# observer.net
KiCad netlist of a schematic drawn in EAGLE
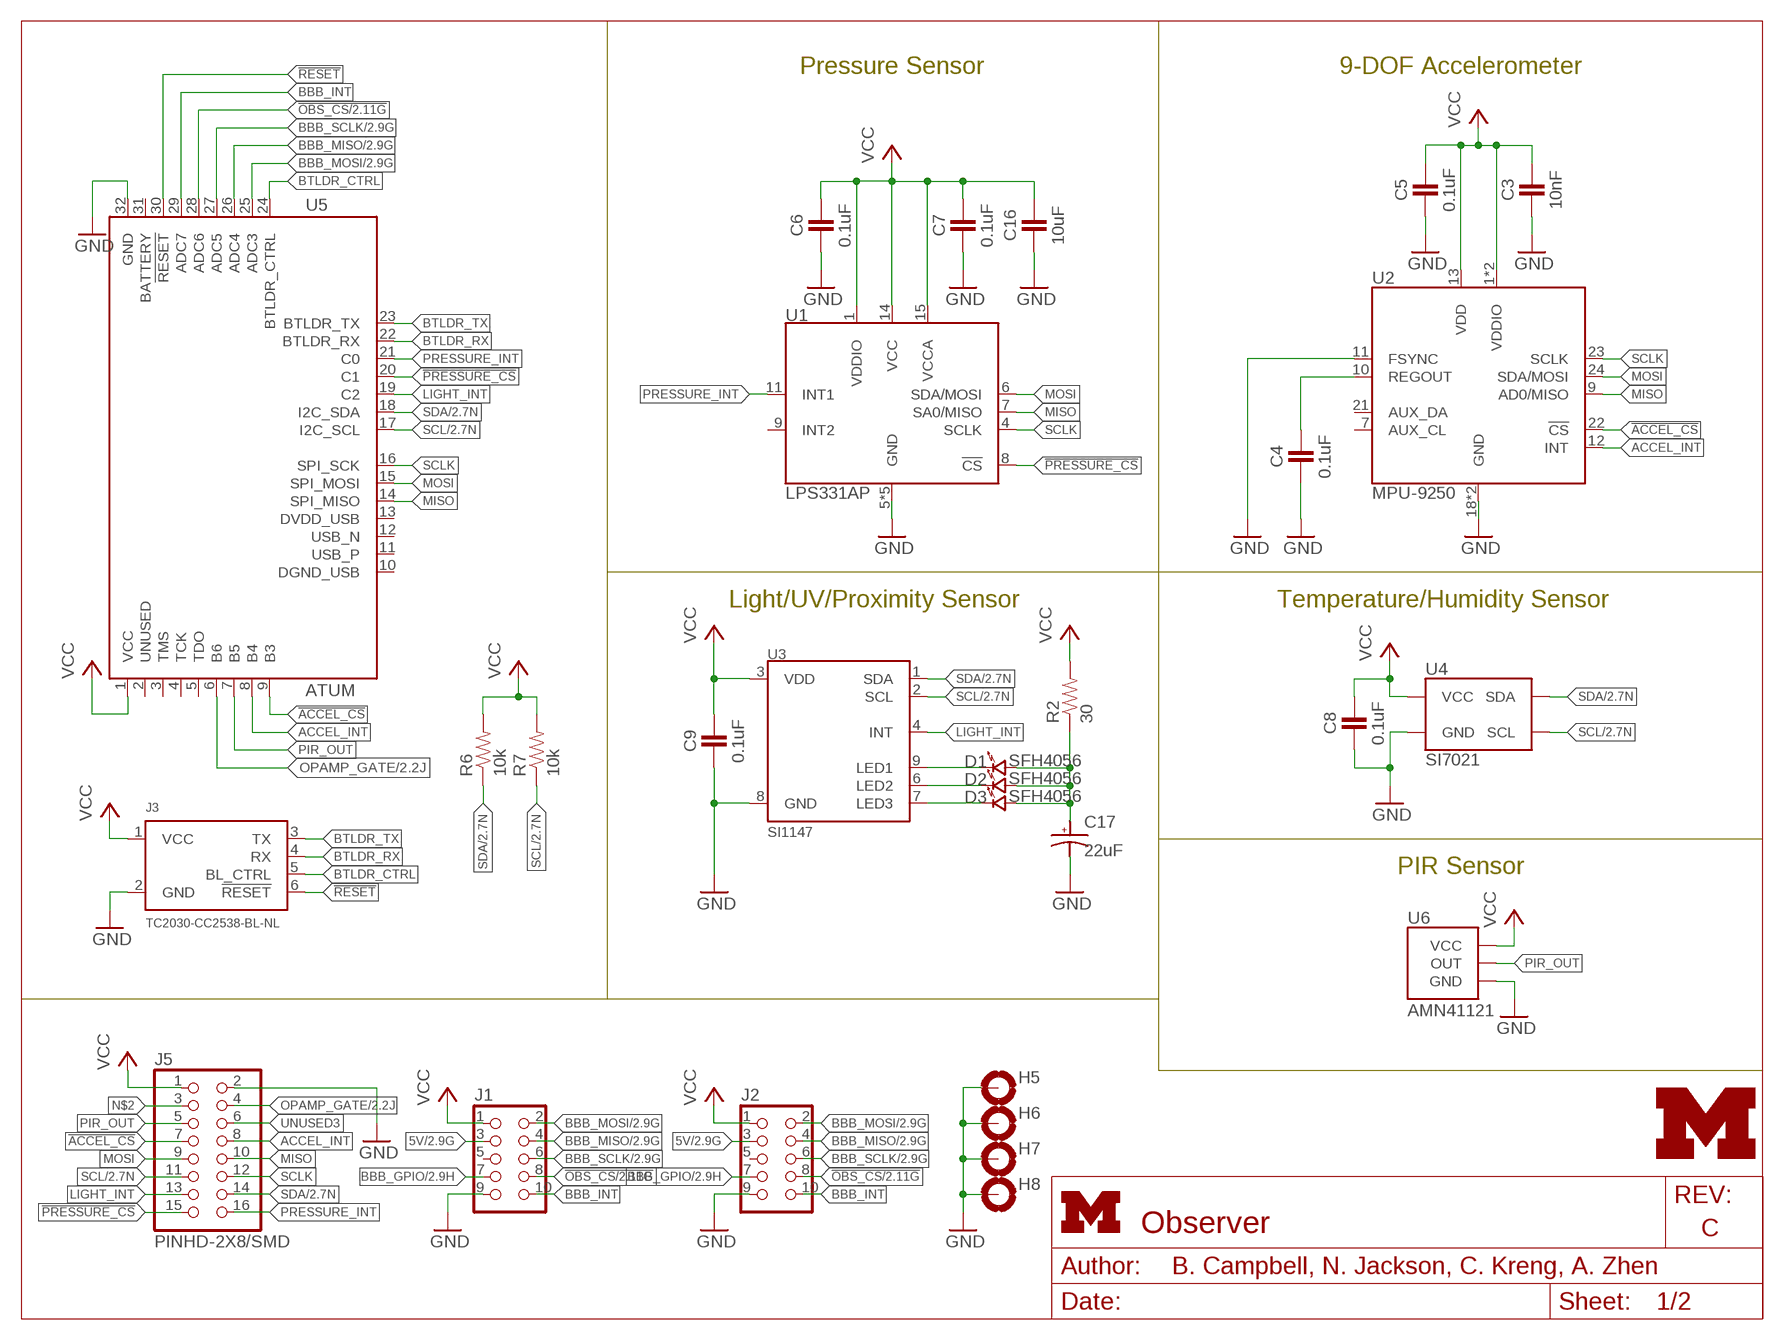
[diagram p0: schematic, sheet 1]
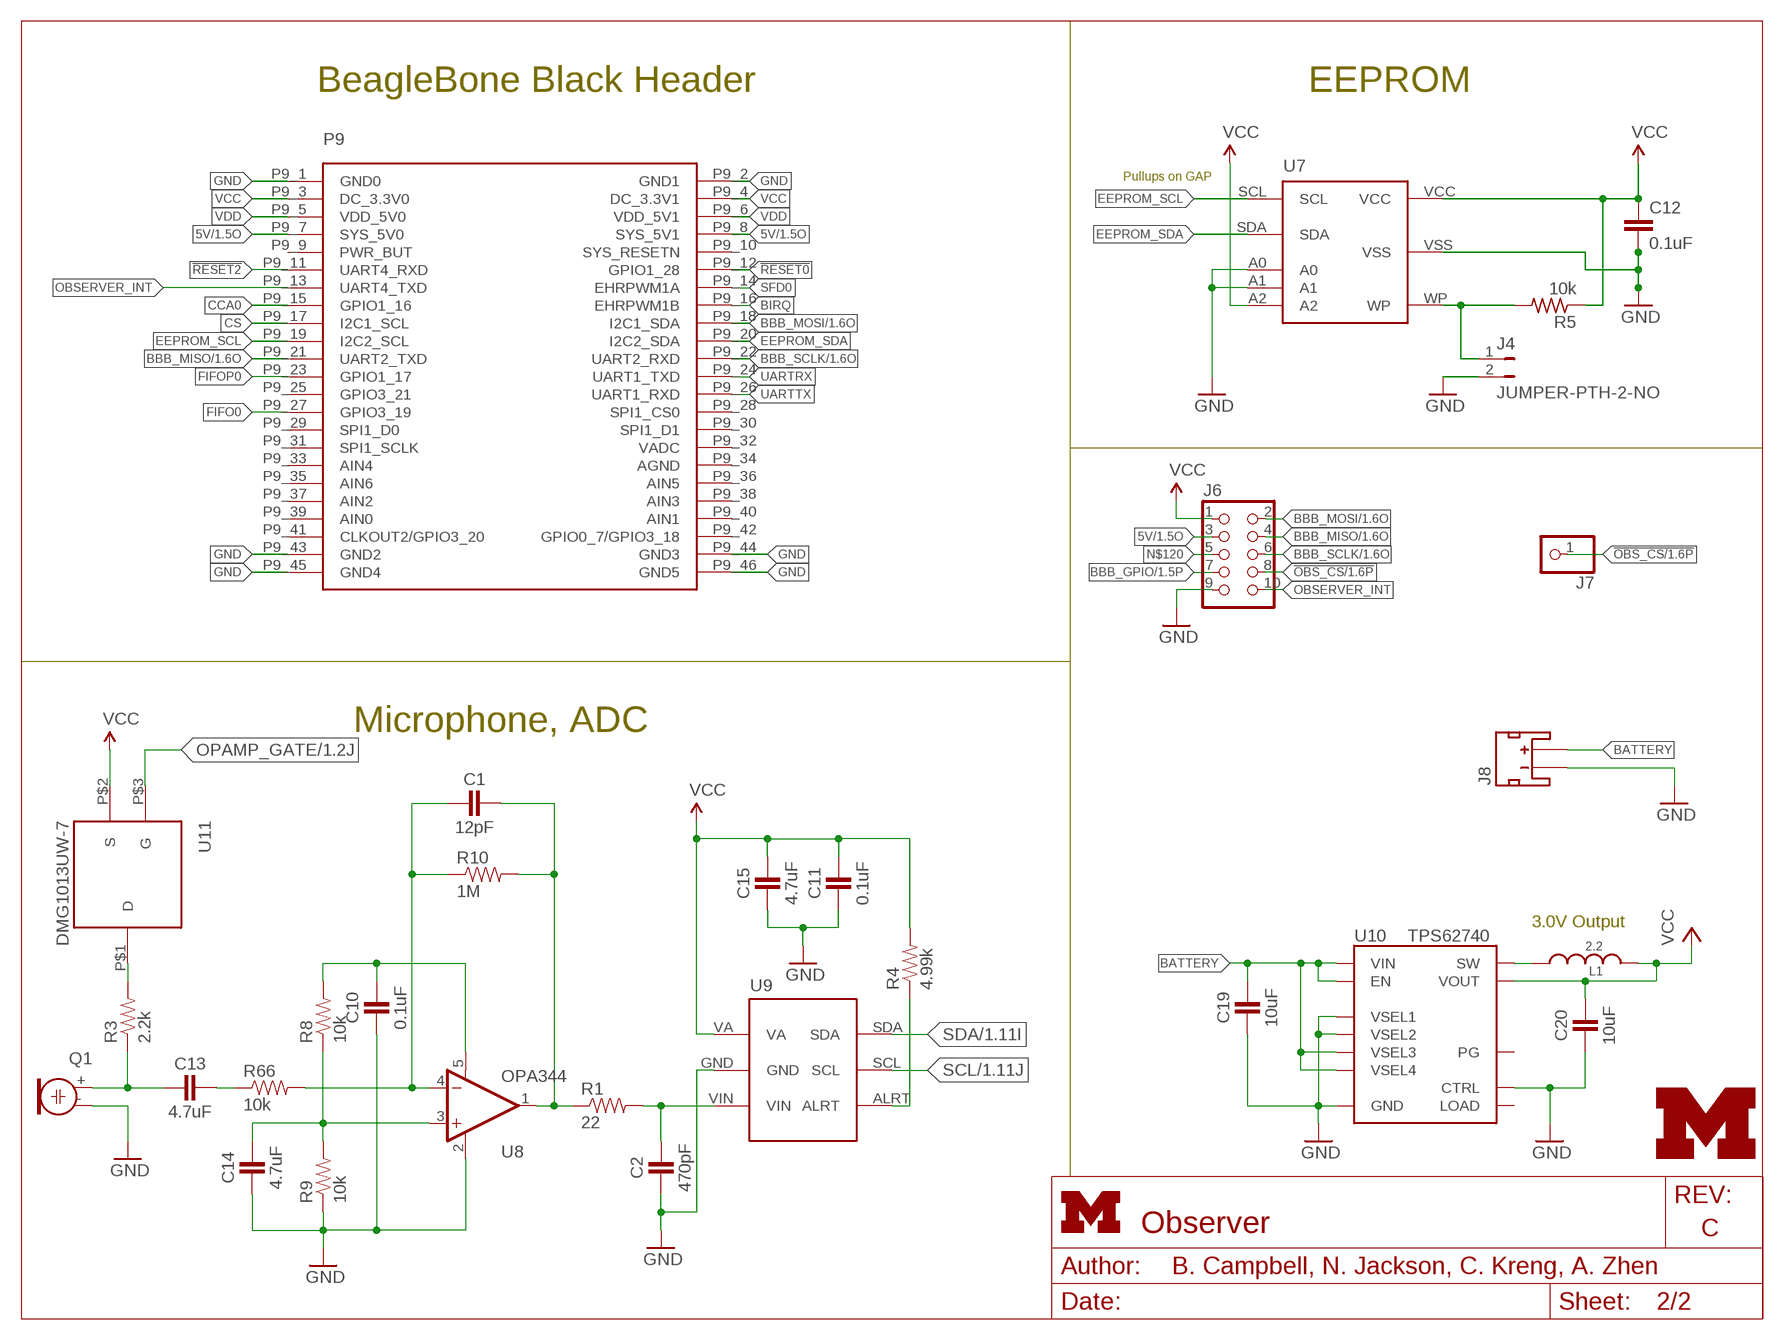
[diagram p1: schematic, sheet 2]

(export (version "E")
  (design (tool "Eeschema 10.0.6"))
  (components
    (comp (ref "C1")
      (value "12pF")
      (footprint "eagle-import:0402_CAP")
      (libsource (lib "eagle-import") (part "CAPACITOR"))
    )
    (comp (ref "C2")
      (value "470pF")
      (footprint "eagle-import:0402_CAP")
      (libsource (lib "eagle-import") (part "CAPACITOR"))
    )
    (comp (ref "C10")
      (value "0.1uF")
      (footprint "eagle-import:0402_CAP")
      (libsource (lib "eagle-import") (part "CAPACITOR"))
    )
    (comp (ref "C11")
      (value "0.1uF")
      (footprint "eagle-import:0402_CAP")
      (libsource (lib "eagle-import") (part "CAPACITOR"))
    )
    (comp (ref "C12")
      (value "0.1uF")
      (footprint "eagle-import:C0402")
      (libsource (lib "eagle-import") (part "C-EUC0402"))
    )
    (comp (ref "C13")
      (value "4.7uF")
      (footprint "eagle-import:0402_CAP")
      (libsource (lib "eagle-import") (part "CAPACITOR"))
    )
    (comp (ref "C14")
      (value "4.7uF")
      (footprint "eagle-import:0402_CAP")
      (libsource (lib "eagle-import") (part "CAPACITOR"))
    )
    (comp (ref "C15")
      (value "4.7uF")
      (footprint "eagle-import:0402_CAP")
      (libsource (lib "eagle-import") (part "CAPACITOR"))
    )
    (comp (ref "C19")
      (value "10uF")
      (footprint "eagle-import:0603_CAP")
      (libsource (lib "eagle-import") (part "CAPACITOR0603_CAP"))
    )
    (comp (ref "C20")
      (value "10uF")
      (footprint "eagle-import:0603_CAP")
      (libsource (lib "eagle-import") (part "CAPACITOR0603_CAP"))
    )
    (comp (ref "J4")
      (value "JUMPER-PTH-2-NO")
      (footprint "eagle-import:PTH-JUMPER-2-NO_NO_SILK")
      (libsource (lib "eagle-import") (part "JUMPER-PTH-2-NO"))
    )
    (comp (ref "J6")
      (value "CON_HEADER_2X05-PTH+SHROUDED_A")
      (footprint "eagle-import:PINSHRD_PTH_2X05")
      (libsource (lib "eagle-import") (part "CON_HEADER_2X05-PTH+SHROUDED_A"))
    )
    (comp (ref "J7")
      (value "PINHD-1X1")
      (footprint "eagle-import:1X01")
      (libsource (lib "eagle-import") (part "PINHD-1X1"))
    )
    (comp (ref "J8")
      (value "JST_2MM_MALE")
      (footprint "eagle-import:JST-2-SMD")
      (libsource (lib "eagle-import") (part "JST_2MM_MALE"))
    )
    (comp (ref "L1")
      (value "2.2")
      (footprint "eagle-import:MIPSZ201D")
      (libsource (lib "eagle-import") (part "MIPSZ2012D"))
    )
    (comp (ref "LOGO2")
      (value "UMICH_SOLID_TINY")
      (footprint "eagle-import:UMICH_SOLID_50MIL")
      (libsource (lib "eagle-import") (part "UMICH_SOLID_TINY"))
    )
    (comp (ref "P9/P8")
      (value "BBB_HEADER")
      (footprint "eagle-import:BBB_HEADERS")
      (libsource (lib "eagle-import") (part "BBB_HEADER"))
    )
    (comp (ref "Q1")
      (value "ELECTRET")
      (footprint "eagle-import:ELECTRET_9.7")
      (libsource (lib "eagle-import") (part "ELECTRET"))
    )
    (comp (ref "R1")
      (value "22")
      (footprint "eagle-import:0402_RES")
      (libsource (lib "eagle-import") (part "RESISTOR0402_RES"))
    )
    (comp (ref "R3")
      (value "2.2k")
      (footprint "eagle-import:0402_RES")
      (libsource (lib "eagle-import") (part "RESISTOR0402_RES"))
    )
    (comp (ref "R4")
      (value "4.99k")
      (footprint "eagle-import:0402_RES")
      (libsource (lib "eagle-import") (part "RESISTOR0402_RES"))
    )
    (comp (ref "R5")
      (value "10k")
      (footprint "eagle-import:R0402")
      (libsource (lib "eagle-import") (part "R-US_R0402"))
    )
    (comp (ref "R8")
      (value "10k")
      (footprint "eagle-import:0402_RES")
      (libsource (lib "eagle-import") (part "RESISTOR0402_RES"))
    )
    (comp (ref "R9")
      (value "10k")
      (footprint "eagle-import:0402_RES")
      (libsource (lib "eagle-import") (part "RESISTOR0402_RES"))
    )
    (comp (ref "R10")
      (value "1M")
      (footprint "eagle-import:0402_RES")
      (libsource (lib "eagle-import") (part "RESISTOR0402_RES"))
    )
    (comp (ref "R66")
      (value "10k")
      (footprint "eagle-import:0402_RES")
      (libsource (lib "eagle-import") (part "RESISTOR0402_RES"))
    )
    (comp (ref "U7")
      (value "CAT24C256WI-GT3")
      (footprint "eagle-import:CAT24C256WI-GT3")
      (libsource (lib "eagle-import") (part "CAT24C256WI-GT3"))
    )
    (comp (ref "U8")
      (value "OPA344")
      (footprint "eagle-import:SOT23-5")
      (libsource (lib "eagle-import") (part "OPA344"))
    )
    (comp (ref "U9")
      (value "ADC121C021")
      (footprint "eagle-import:ADC121C021")
      (libsource (lib "eagle-import") (part "ADC121C021"))
    )
    (comp (ref "U10")
      (value "TPS62740")
      (footprint "eagle-import:R-PWSON-12")
      (libsource (lib "eagle-import") (part "TPS62740"))
    )
    (comp (ref "U11")
      (value "DMG1013UW-7")
      (footprint "eagle-import:SOT-323")
      (libsource (lib "eagle-import") (part "DMG1013UW-7"))
    )
    (comp (ref "C3")
      (value "10nF")
      (footprint "eagle-import:0402_CAP")
      (libsource (lib "eagle-import") (part "CAPACITOR"))
    )
    (comp (ref "C4")
      (value "0.1uF")
      (footprint "eagle-import:0402_CAP")
      (libsource (lib "eagle-import") (part "CAPACITOR"))
    )
    (comp (ref "C5")
      (value "0.1uF")
      (footprint "eagle-import:0402_CAP")
      (libsource (lib "eagle-import") (part "CAPACITOR"))
    )
    (comp (ref "C6")
      (value "0.1uF")
      (footprint "eagle-import:0402_CAP")
      (libsource (lib "eagle-import") (part "CAPACITOR"))
    )
    (comp (ref "C7")
      (value "0.1uF")
      (footprint "eagle-import:0402_CAP")
      (libsource (lib "eagle-import") (part "CAPACITOR"))
    )
    (comp (ref "C8")
      (value "0.1uF")
      (footprint "eagle-import:0402_CAP")
      (libsource (lib "eagle-import") (part "CAPACITOR"))
    )
    (comp (ref "C9")
      (value "0.1uF")
      (footprint "eagle-import:0402_CAP")
      (libsource (lib "eagle-import") (part "CAPACITOR"))
    )
    (comp (ref "C16")
      (value "10uF")
      (footprint "eagle-import:0402_CAP")
      (libsource (lib "eagle-import") (part "CAPACITOR"))
    )
    (comp (ref "C17")
      (value "22uF")
      (footprint "eagle-import:CAP0603")
      (libsource (lib "eagle-import") (part "CAP_POL0603"))
    )
    (comp (ref "D1")
      (value "SFH4056")
      (footprint "eagle-import:SFH4056")
      (libsource (lib "eagle-import") (part "SFH4056"))
    )
    (comp (ref "D2")
      (value "SFH4056")
      (footprint "eagle-import:SFH4056")
      (libsource (lib "eagle-import") (part "SFH4056"))
    )
    (comp (ref "D3")
      (value "SFH4056")
      (footprint "eagle-import:SFH4056")
      (libsource (lib "eagle-import") (part "SFH4056"))
    )
    (comp (ref "H5")
      (value "MOUNT-PAD-ROUND3.2")
      (footprint "eagle-import:3,2-PAD")
      (libsource (lib "eagle-import") (part "MOUNT-PAD-ROUND3.2"))
    )
    (comp (ref "H6")
      (value "MOUNT-PAD-ROUND3.2")
      (footprint "eagle-import:3,2-PAD")
      (libsource (lib "eagle-import") (part "MOUNT-PAD-ROUND3.2"))
    )
    (comp (ref "H7")
      (value "MOUNT-PAD-ROUND3.2")
      (footprint "eagle-import:3,2-PAD")
      (libsource (lib "eagle-import") (part "MOUNT-PAD-ROUND3.2"))
    )
    (comp (ref "H8")
      (value "MOUNT-PAD-ROUND3.2")
      (footprint "eagle-import:3,2-PAD")
      (libsource (lib "eagle-import") (part "MOUNT-PAD-ROUND3.2"))
    )
    (comp (ref "J1")
      (value "CON_HEADER_2X05-SMD+SHROUDED")
      (footprint "eagle-import:PINSHRD_SMT_2X05")
      (libsource (lib "eagle-import") (part "CON_HEADER_2X05-SMD+SHROUDED"))
    )
    (comp (ref "J2")
      (value "CON_HEADER_2X05-SMD+SHROUDED")
      (footprint "eagle-import:PINSHRD_SMT_2X05")
      (libsource (lib "eagle-import") (part "CON_HEADER_2X05-SMD+SHROUDED"))
    )
    (comp (ref "J3")
      (value "TC2030-CC2538-BL-NL")
      (footprint "eagle-import:TC2030-IDC-NL")
      (libsource (lib "eagle-import") (part "TC2030-CC2538-BL-NL"))
    )
    (comp (ref "J5")
      (value "PINHD-2X8/SMD")
      (footprint "eagle-import:2X8_SMD")
      (libsource (lib "eagle-import") (part "PINHD-2X8/SMD"))
    )
    (comp (ref "LOGO1")
      (value "UMICH_SOLID_TINY")
      (footprint "eagle-import:UMICH_SOLID_50MIL")
      (libsource (lib "eagle-import") (part "UMICH_SOLID_TINY"))
    )
    (comp (ref "R2")
      (value "30")
      (footprint "eagle-import:0402_RES")
      (libsource (lib "eagle-import") (part "RESISTOR0402_RES"))
    )
    (comp (ref "R6")
      (value "10k")
      (footprint "eagle-import:0402_RES")
      (libsource (lib "eagle-import") (part "RESISTOR0402_RES"))
    )
    (comp (ref "R7")
      (value "10k")
      (footprint "eagle-import:0402_RES")
      (libsource (lib "eagle-import") (part "RESISTOR0402_RES"))
    )
    (comp (ref "U1")
      (value "LPS331AP")
      (footprint "eagle-import:HCLGA-16_3MM")
      (libsource (lib "eagle-import") (part "LPS331AP"))
    )
    (comp (ref "U2")
      (value "MPU-9250")
      (footprint "eagle-import:QFN-24_3MM")
      (libsource (lib "eagle-import") (part "MPU-9250"))
    )
    (comp (ref "U3")
      (value "SI1147")
      (footprint "eagle-import:QFN-10_2MM")
      (libsource (lib "eagle-import") (part "SI1147"))
    )
    (comp (ref "U4")
      (value "SI7021")
      (footprint "eagle-import:DFN-6_3MM")
      (libsource (lib "eagle-import") (part "SI7021"))
    )
    (comp (ref "U5")
      (value "ATUM")
      (footprint "eagle-import:ATUM")
      (libsource (lib "eagle-import") (part "ATUM"))
    )
    (comp (ref "U6")
      (value "AMN41121")
      (footprint "eagle-import:AMN2")
      (libsource (lib "eagle-import") (part "AMN41121"))
    )
  )
  (nets
    (net (code "1") (name "5V") (class "Default")
      (node (ref "J1") (pin "3") (pinfunction "3_3") (pintype "passive"))
      (node (ref "J2") (pin "3") (pinfunction "3_3") (pintype "passive"))
      (node (ref "J6") (pin "3") (pinfunction "3_3") (pintype "passive"))
      (node (ref "P9/P8") (pin "P9_7") (pinfunction "SYS_5V0_P9_7") (pintype "bidirectional"))
      (node (ref "P9/P8") (pin "P9_8") (pinfunction "SYS_5V1_P9_8") (pintype "bidirectional"))
    )
    (net (code "2") (name "ACCEL_INT") (class "Default")
      (node (ref "J5") (pin "8") (pinfunction "8_8") (pintype "passive"))
      (node (ref "U2") (pin "12") (pinfunction "INT_12") (pintype "bidirectional"))
      (node (ref "U5") (pin "8") (pinfunction "B4_8") (pintype "bidirectional"))
    )
    (net (code "3") (name "BATTERY") (class "Default")
      (node (ref "C19") (pin "1") (pinfunction "1_1") (pintype "bidirectional"))
      (node (ref "J8") (pin "2") (pinfunction "+_2") (pintype "bidirectional"))
      (node (ref "U10") (pin "1") (pinfunction "VIN_1") (pintype "bidirectional"))
      (node (ref "U10") (pin "12") (pinfunction "EN_12") (pintype "bidirectional"))
      (node (ref "U10") (pin "8") (pinfunction "VSEL4_8") (pintype "bidirectional"))
      (node (ref "U10") (pin "9") (pinfunction "VSEL3_9") (pintype "bidirectional"))
    )
    (net (code "4") (name "BBB_GPIO") (class "Default")
      (node (ref "J1") (pin "7") (pinfunction "7_7") (pintype "passive"))
      (node (ref "J2") (pin "7") (pinfunction "7_7") (pintype "passive"))
      (node (ref "J6") (pin "7") (pinfunction "7_7") (pintype "passive"))
    )
    (net (code "5") (name "BBB_INT") (class "Default")
      (node (ref "J1") (pin "10") (pinfunction "10_10") (pintype "passive"))
      (node (ref "J2") (pin "10") (pinfunction "10_10") (pintype "passive"))
      (node (ref "U5") (pin "29") (pinfunction "ADC7_29") (pintype "bidirectional"))
    )
    (net (code "6") (name "BBB_MISO") (class "Default")
      (node (ref "J1") (pin "4") (pinfunction "4_4") (pintype "passive"))
      (node (ref "J2") (pin "4") (pinfunction "4_4") (pintype "passive"))
      (node (ref "J6") (pin "4") (pinfunction "4_4") (pintype "passive"))
      (node (ref "P9/P8") (pin "P9_21") (pinfunction "UART2_TXD_P9_21") (pintype "bidirectional"))
      (node (ref "U5") (pin "26") (pinfunction "ADC4_26") (pintype "bidirectional"))
    )
    (net (code "7") (name "BBB_MOSI") (class "Default")
      (node (ref "J1") (pin "2") (pinfunction "2_2") (pintype "passive"))
      (node (ref "J2") (pin "2") (pinfunction "2_2") (pintype "passive"))
      (node (ref "J6") (pin "2") (pinfunction "2_2") (pintype "passive"))
      (node (ref "P9/P8") (pin "P9_18") (pinfunction "I2C1_SDA_P9_18") (pintype "bidirectional"))
      (node (ref "U5") (pin "25") (pinfunction "ADC3_25") (pintype "bidirectional"))
    )
    (net (code "8") (name "BBB_SCLK") (class "Default")
      (node (ref "J1") (pin "6") (pinfunction "6_6") (pintype "passive"))
      (node (ref "J2") (pin "6") (pinfunction "6_6") (pintype "passive"))
      (node (ref "J6") (pin "6") (pinfunction "6_6") (pintype "passive"))
      (node (ref "P9/P8") (pin "P9_22") (pinfunction "UART2_RXD_P9_22") (pintype "bidirectional"))
      (node (ref "U5") (pin "27") (pinfunction "ADC5_27") (pintype "bidirectional"))
    )
    (net (code "9") (name "BIRQ") (class "Default")
      (node (ref "P9/P8") (pin "P9_16") (pinfunction "EHRPWM1B_P9_16") (pintype "bidirectional"))
    )
    (net (code "10") (name "BTLDR_CTRL") (class "Default")
      (node (ref "J3") (pin "5") (pinfunction "BL_CTRL_5") (pintype "bidirectional"))
      (node (ref "U5") (pin "24") (pinfunction "BTLDR_CTRL_24") (pintype "bidirectional"))
    )
    (net (code "11") (name "BTLDR_RX") (class "Default")
      (node (ref "J3") (pin "4") (pinfunction "RX_4") (pintype "bidirectional"))
      (node (ref "U5") (pin "22") (pinfunction "BTLDR_RX_22") (pintype "bidirectional"))
    )
    (net (code "12") (name "BTLDR_TX") (class "Default")
      (node (ref "J3") (pin "3") (pinfunction "TX_3") (pintype "bidirectional"))
      (node (ref "U5") (pin "23") (pinfunction "BTLDR_TX_23") (pintype "bidirectional"))
    )
    (net (code "13") (name "CCA0") (class "Default")
      (node (ref "P9/P8") (pin "P9_15") (pinfunction "GPIO1_16_P9_15") (pintype "bidirectional"))
    )
    (net (code "14") (name "CS") (class "Default")
      (node (ref "P9/P8") (pin "P9_17") (pinfunction "I2C1_SCL_P9_17") (pintype "bidirectional"))
    )
    (net (code "15") (name "EEPROM_SCL") (class "Default")
      (node (ref "P9/P8") (pin "P9_19") (pinfunction "I2C2_SCL_P9_19") (pintype "bidirectional"))
      (node (ref "U7") (pin "SCL") (pinfunction "SCL_SCL") (pintype "bidirectional"))
    )
    (net (code "16") (name "EEPROM_SDA") (class "Default")
      (node (ref "P9/P8") (pin "P9_20") (pinfunction "I2C2_SDA_P9_20") (pintype "bidirectional"))
      (node (ref "U7") (pin "SDA") (pinfunction "SDA_SDA") (pintype "bidirectional"))
    )
    (net (code "17") (name "FIFO0") (class "Default")
      (node (ref "P9/P8") (pin "P9_27") (pinfunction "GPIO3_19_P9_27") (pintype "bidirectional"))
    )
    (net (code "18") (name "FIFOP0") (class "Default")
      (node (ref "P9/P8") (pin "P9_23") (pinfunction "GPIO1_17_P9_23") (pintype "bidirectional"))
    )
    (net (code "19") (name "GND") (class "Default")
      (node (ref "C10") (pin "2") (pinfunction "2_2") (pintype "bidirectional"))
      (node (ref "C11") (pin "2") (pinfunction "2_2") (pintype "bidirectional"))
      (node (ref "C12") (pin "2") (pinfunction "2_2") (pintype "passive"))
      (node (ref "C14") (pin "2") (pinfunction "2_2") (pintype "bidirectional"))
      (node (ref "C15") (pin "2") (pinfunction "2_2") (pintype "bidirectional"))
      (node (ref "C16") (pin "2") (pinfunction "2_2") (pintype "bidirectional"))
      (node (ref "C17") (pin "NEG") (pinfunction "ANODE_NEG") (pintype "bidirectional"))
      (node (ref "C19") (pin "2") (pinfunction "2_2") (pintype "bidirectional"))
      (node (ref "C2") (pin "2") (pinfunction "2_2") (pintype "bidirectional"))
      (node (ref "C20") (pin "2") (pinfunction "2_2") (pintype "bidirectional"))
      (node (ref "C3") (pin "2") (pinfunction "2_2") (pintype "bidirectional"))
      (node (ref "C4") (pin "2") (pinfunction "2_2") (pintype "bidirectional"))
      (node (ref "C5") (pin "2") (pinfunction "2_2") (pintype "bidirectional"))
      (node (ref "C6") (pin "2") (pinfunction "2_2") (pintype "bidirectional"))
      (node (ref "C7") (pin "2") (pinfunction "2_2") (pintype "bidirectional"))
      (node (ref "C8") (pin "2") (pinfunction "2_2") (pintype "bidirectional"))
      (node (ref "C9") (pin "2") (pinfunction "2_2") (pintype "bidirectional"))
      (node (ref "H5") (pin "B3,2") (pinfunction "MOUNT_B3,2") (pintype "passive"))
      (node (ref "H6") (pin "B3,2") (pinfunction "MOUNT_B3,2") (pintype "passive"))
      (node (ref "H7") (pin "B3,2") (pinfunction "MOUNT_B3,2") (pintype "passive"))
      (node (ref "H8") (pin "B3,2") (pinfunction "MOUNT_B3,2") (pintype "passive"))
      (node (ref "J1") (pin "9") (pinfunction "9_9") (pintype "passive"))
      (node (ref "J2") (pin "9") (pinfunction "9_9") (pintype "passive"))
      (node (ref "J3") (pin "2") (pinfunction "GND_2") (pintype "bidirectional"))
      (node (ref "J4") (pin "2") (pinfunction "2_2") (pintype "passive"))
      (node (ref "J5") (pin "2") (pinfunction "2_2") (pintype "passive"))
      (node (ref "J6") (pin "9") (pinfunction "9_9") (pintype "passive"))
      (node (ref "J8") (pin "1") (pinfunction "-_1") (pintype "bidirectional"))
      (node (ref "P9/P8") (pin "P9_1") (pinfunction "GND0_P9_1") (pintype "bidirectional"))
      (node (ref "P9/P8") (pin "P9_2") (pinfunction "GND1_P9_2") (pintype "bidirectional"))
      (node (ref "P9/P8") (pin "P9_43") (pinfunction "GND2_P9_43") (pintype "bidirectional"))
      (node (ref "P9/P8") (pin "P9_44") (pinfunction "GND3_P9_44") (pintype "bidirectional"))
      (node (ref "P9/P8") (pin "P9_45") (pinfunction "GND4_P9_45") (pintype "bidirectional"))
      (node (ref "P9/P8") (pin "P9_46") (pinfunction "GND5_P9_46") (pintype "bidirectional"))
      (node (ref "Q1") (pin "-") (pinfunction "1_-") (pintype "passive"))
      (node (ref "R9") (pin "1") (pinfunction "1_1") (pintype "passive"))
      (node (ref "U1") (pin "10") (pinfunction "GND_10") (pintype "bidirectional"))
      (node (ref "U1") (pin "12") (pinfunction "GND_12") (pintype "bidirectional"))
      (node (ref "U1") (pin "13") (pinfunction "GND_13") (pintype "bidirectional"))
      (node (ref "U1") (pin "16") (pinfunction "GND_16") (pintype "bidirectional"))
      (node (ref "U1") (pin "5") (pinfunction "GND_5") (pintype "bidirectional"))
      (node (ref "U10") (pin "10") (pinfunction "VSEL2_10") (pintype "bidirectional"))
      (node (ref "U10") (pin "11") (pinfunction "VSEL1_11") (pintype "bidirectional"))
      (node (ref "U10") (pin "3") (pinfunction "GND_3") (pintype "bidirectional"))
      (node (ref "U10") (pin "4") (pinfunction "CTRL_4") (pintype "bidirectional"))
      (node (ref "U10") (pin "NC") (pinfunction "GND_NC") (pintype "bidirectional"))
      (node (ref "U2") (pin "11") (pinfunction "FSYNC_11") (pintype "bidirectional"))
      (node (ref "U2") (pin "18") (pinfunction "GND_18") (pintype "bidirectional"))
      (node (ref "U2") (pin "20") (pinfunction "GND_20") (pintype "bidirectional"))
      (node (ref "U3") (pin "8") (pinfunction "GND_8") (pintype "bidirectional"))
      (node (ref "U4") (pin "2") (pinfunction "GND_2") (pintype "bidirectional"))
      (node (ref "U5") (pin "32") (pinfunction "GND_32") (pintype "bidirectional"))
      (node (ref "U6") (pin "GND") (pinfunction "GND_GND") (pintype "bidirectional"))
      (node (ref "U7") (pin "A0") (pinfunction "A0_A0") (pintype "bidirectional"))
      (node (ref "U7") (pin "A1") (pinfunction "A1_A1") (pintype "bidirectional"))
      (node (ref "U7") (pin "VSS") (pinfunction "VSS_VSS") (pintype "bidirectional"))
      (node (ref "U8") (pin "2") (pinfunction "V-_2") (pintype "power_in"))
      (node (ref "U9") (pin "GND") (pinfunction "GND_GND") (pintype "bidirectional"))
    )
    (net (code "20") (name "LIGHT_INT") (class "Default")
      (node (ref "J5") (pin "13") (pinfunction "13_13") (pintype "passive"))
      (node (ref "U3") (pin "4") (pinfunction "INT_4") (pintype "bidirectional"))
      (node (ref "U5") (pin "19") (pinfunction "C2_19") (pintype "bidirectional"))
    )
    (net (code "21") (name "MISO") (class "Default")
      (node (ref "J5") (pin "10") (pinfunction "10_10") (pintype "passive"))
      (node (ref "U1") (pin "7") (pinfunction "SA0/MISO_7") (pintype "bidirectional"))
      (node (ref "U2") (pin "9") (pinfunction "AD0/MISO_9") (pintype "bidirectional"))
      (node (ref "U5") (pin "14") (pinfunction "SPI_MISO_14") (pintype "bidirectional"))
    )
    (net (code "22") (name "MOSI") (class "Default")
      (node (ref "J5") (pin "9") (pinfunction "9_9") (pintype "passive"))
      (node (ref "U1") (pin "6") (pinfunction "SDA/MOSI_6") (pintype "bidirectional"))
      (node (ref "U2") (pin "24") (pinfunction "SDA/MOSI_24") (pintype "bidirectional"))
      (node (ref "U5") (pin "15") (pinfunction "SPI_MOSI_15") (pintype "bidirectional"))
    )
    (net (code "23") (name "N$2") (class "Default")
      (node (ref "J5") (pin "3") (pinfunction "3_3") (pintype "passive"))
    )
    (net (code "24") (name "N$120") (class "Default")
      (node (ref "J6") (pin "5") (pinfunction "5_5") (pintype "passive"))
    )
    (net (code "25") (name "Net-(C2-Pad1)") (class "Default")
      (node (ref "C2") (pin "1") (pinfunction "1_1") (pintype "bidirectional"))
      (node (ref "R1") (pin "2") (pinfunction "2_2") (pintype "passive"))
      (node (ref "U9") (pin "VIN") (pinfunction "VIN_VIN") (pintype "bidirectional"))
    )
    (net (code "26") (name "Net-(C13-Pad1)") (class "Default")
      (node (ref "C13") (pin "1") (pinfunction "1_1") (pintype "bidirectional"))
      (node (ref "R66") (pin "1") (pinfunction "1_1") (pintype "passive"))
    )
    (net (code "27") (name "Net-(C17-CATHODE)") (class "Default")
      (node (ref "C17") (pin "POS") (pinfunction "CATHODE_POS") (pintype "bidirectional"))
      (node (ref "D1") (pin "ANODE") (pinfunction "ANODE_ANODE") (pintype "bidirectional"))
      (node (ref "D2") (pin "ANODE") (pinfunction "ANODE_ANODE") (pintype "bidirectional"))
      (node (ref "D3") (pin "ANODE") (pinfunction "ANODE_ANODE") (pintype "bidirectional"))
      (node (ref "R2") (pin "1") (pinfunction "1_1") (pintype "passive"))
    )
    (net (code "28") (name "Net-(J4-Pad1)") (class "Default")
      (node (ref "J4") (pin "1") (pinfunction "1_1") (pintype "passive"))
      (node (ref "R5") (pin "2") (pinfunction "2_2") (pintype "passive"))
      (node (ref "U7") (pin "WP") (pinfunction "WP_WP") (pintype "bidirectional"))
    )
    (net (code "29") (name "Net-(Q1-2)") (class "Default")
      (node (ref "C13") (pin "2") (pinfunction "2_2") (pintype "bidirectional"))
      (node (ref "Q1") (pin "+") (pinfunction "2_+") (pintype "passive"))
      (node (ref "R3") (pin "1") (pinfunction "1_1") (pintype "passive"))
    )
    (net (code "30") (name "Net-(R4-Pad1)") (class "Default")
      (node (ref "R4") (pin "1") (pinfunction "1_1") (pintype "passive"))
      (node (ref "U9") (pin "ALRT") (pinfunction "ALRT_ALRT") (pintype "bidirectional"))
    )
    (net (code "31") (name "Net-(U2-REGOUT)") (class "Default")
      (node (ref "C4") (pin "1") (pinfunction "1_1") (pintype "bidirectional"))
      (node (ref "U2") (pin "10") (pinfunction "REGOUT_10") (pintype "bidirectional"))
    )
    (net (code "32") (name "Net-(U3-LED1)") (class "Default")
      (node (ref "D1") (pin "CATHODE") (pinfunction "CATHODE_CATHODE") (pintype "bidirectional"))
      (node (ref "U3") (pin "9") (pinfunction "LED1_9") (pintype "bidirectional"))
    )
    (net (code "33") (name "Net-(U3-LED2)") (class "Default")
      (node (ref "D2") (pin "CATHODE") (pinfunction "CATHODE_CATHODE") (pintype "bidirectional"))
      (node (ref "U3") (pin "6") (pinfunction "LED2_6") (pintype "bidirectional"))
    )
    (net (code "34") (name "Net-(U3-LED3)") (class "Default")
      (node (ref "D3") (pin "CATHODE") (pinfunction "CATHODE_CATHODE") (pintype "bidirectional"))
      (node (ref "U3") (pin "7") (pinfunction "LED3_7") (pintype "bidirectional"))
    )
    (net (code "35") (name "Net-(U8-+IN)") (class "Default")
      (node (ref "C14") (pin "1") (pinfunction "1_1") (pintype "bidirectional"))
      (node (ref "R8") (pin "1") (pinfunction "1_1") (pintype "passive"))
      (node (ref "R9") (pin "2") (pinfunction "2_2") (pintype "passive"))
      (node (ref "U8") (pin "3") (pinfunction "+IN_3") (pintype "input"))
    )
    (net (code "36") (name "Net-(U8--IN)") (class "Default")
      (node (ref "C1") (pin "2") (pinfunction "2_2") (pintype "bidirectional"))
      (node (ref "R10") (pin "1") (pinfunction "1_1") (pintype "passive"))
      (node (ref "R66") (pin "2") (pinfunction "2_2") (pintype "passive"))
      (node (ref "U8") (pin "4") (pinfunction "-IN_4") (pintype "input"))
    )
    (net (code "37") (name "Net-(U8-OUT)") (class "Default")
      (node (ref "C1") (pin "1") (pinfunction "1_1") (pintype "bidirectional"))
      (node (ref "R1") (pin "1") (pinfunction "1_1") (pintype "passive"))
      (node (ref "R10") (pin "2") (pinfunction "2_2") (pintype "passive"))
      (node (ref "U8") (pin "1") (pinfunction "OUT_1") (pintype "output"))
    )
    (net (code "38") (name "Net-(U8-V+)") (class "Default")
      (node (ref "C10") (pin "1") (pinfunction "1_1") (pintype "bidirectional"))
      (node (ref "R8") (pin "2") (pinfunction "2_2") (pintype "passive"))
      (node (ref "U8") (pin "5") (pinfunction "V+_5") (pintype "power_in"))
    )
    (net (code "39") (name "Net-(U10-SW)") (class "Default")
      (node (ref "L1") (pin "1") (pinfunction "1_1") (pintype "bidirectional"))
      (node (ref "U10") (pin "2") (pinfunction "SW_2") (pintype "bidirectional"))
    )
    (net (code "40") (name "Net-(U11-D)") (class "Default")
      (node (ref "R3") (pin "2") (pinfunction "2_2") (pintype "passive"))
      (node (ref "U11") (pin "P$1") (pinfunction "D_P$1") (pintype "bidirectional"))
    )
    (net (code "41") (name "OBSERVER_INT") (class "Default")
      (node (ref "J6") (pin "10") (pinfunction "10_10") (pintype "passive"))
      (node (ref "P9/P8") (pin "P9_13") (pinfunction "UART4_TXD_P9_13") (pintype "bidirectional"))
    )
    (net (code "42") (name "OPAMP_GATE") (class "Default")
      (node (ref "J5") (pin "4") (pinfunction "4_4") (pintype "passive"))
      (node (ref "U11") (pin "P$3") (pinfunction "G_P$3") (pintype "bidirectional"))
      (node (ref "U5") (pin "6") (pinfunction "B6_6") (pintype "bidirectional"))
    )
    (net (code "43") (name "PIR_OUT") (class "Default")
      (node (ref "J5") (pin "5") (pinfunction "5_5") (pintype "passive"))
      (node (ref "U5") (pin "7") (pinfunction "B5_7") (pintype "bidirectional"))
      (node (ref "U6") (pin "OUT") (pinfunction "OUT_OUT") (pintype "bidirectional"))
    )
    (net (code "44") (name "PRESSURE_INT") (class "Default")
      (node (ref "J5") (pin "16") (pinfunction "16_16") (pintype "passive"))
      (node (ref "U1") (pin "11") (pinfunction "INT1_11") (pintype "bidirectional"))
      (node (ref "U5") (pin "21") (pinfunction "C0_21") (pintype "bidirectional"))
    )
    (net (code "45") (name "SCL") (class "Default")
      (node (ref "J5") (pin "11") (pinfunction "11_11") (pintype "passive"))
      (node (ref "R7") (pin "1") (pinfunction "1_1") (pintype "passive"))
      (node (ref "U3") (pin "2") (pinfunction "SCL_2") (pintype "bidirectional"))
      (node (ref "U4") (pin "6") (pinfunction "SCL_6") (pintype "bidirectional"))
      (node (ref "U5") (pin "17") (pinfunction "I2C_SCL_17") (pintype "bidirectional"))
      (node (ref "U9") (pin "SCL") (pinfunction "SCL_SCL") (pintype "bidirectional"))
    )
    (net (code "46") (name "SCLK") (class "Default")
      (node (ref "J5") (pin "12") (pinfunction "12_12") (pintype "passive"))
      (node (ref "U1") (pin "4") (pinfunction "SCLK_4") (pintype "bidirectional"))
      (node (ref "U2") (pin "23") (pinfunction "SCLK_23") (pintype "bidirectional"))
      (node (ref "U5") (pin "16") (pinfunction "SPI_SCK_16") (pintype "bidirectional"))
    )
    (net (code "47") (name "SDA") (class "Default")
      (node (ref "J5") (pin "14") (pinfunction "14_14") (pintype "passive"))
      (node (ref "R6") (pin "1") (pinfunction "1_1") (pintype "passive"))
      (node (ref "U3") (pin "1") (pinfunction "SDA_1") (pintype "bidirectional"))
      (node (ref "U4") (pin "1") (pinfunction "SDA_1") (pintype "bidirectional"))
      (node (ref "U5") (pin "18") (pinfunction "I2C_SDA_18") (pintype "bidirectional"))
      (node (ref "U9") (pin "SDA") (pinfunction "SDA_SDA") (pintype "bidirectional"))
    )
    (net (code "48") (name "SFD0") (class "Default")
      (node (ref "P9/P8") (pin "P9_14") (pinfunction "EHRPWM1A_P9_14") (pintype "bidirectional"))
    )
    (net (code "49") (name "UARTRX") (class "Default")
      (node (ref "P9/P8") (pin "P9_24") (pinfunction "UART1_TXD_P9_24") (pintype "bidirectional"))
    )
    (net (code "50") (name "UARTTX") (class "Default")
      (node (ref "P9/P8") (pin "P9_26") (pinfunction "UART1_RXD_P9_26") (pintype "bidirectional"))
    )
    (net (code "51") (name "UNUSED3") (class "Default")
      (node (ref "J5") (pin "6") (pinfunction "6_6") (pintype "passive"))
    )
    (net (code "52") (name "VCC") (class "Default")
      (node (ref "C11") (pin "1") (pinfunction "1_1") (pintype "bidirectional"))
      (node (ref "C12") (pin "1") (pinfunction "1_1") (pintype "passive"))
      (node (ref "C15") (pin "1") (pinfunction "1_1") (pintype "bidirectional"))
      (node (ref "C16") (pin "1") (pinfunction "1_1") (pintype "bidirectional"))
      (node (ref "C20") (pin "1") (pinfunction "1_1") (pintype "bidirectional"))
      (node (ref "C3") (pin "1") (pinfunction "1_1") (pintype "bidirectional"))
      (node (ref "C5") (pin "1") (pinfunction "1_1") (pintype "bidirectional"))
      (node (ref "C6") (pin "1") (pinfunction "1_1") (pintype "bidirectional"))
      (node (ref "C7") (pin "1") (pinfunction "1_1") (pintype "bidirectional"))
      (node (ref "C8") (pin "1") (pinfunction "1_1") (pintype "bidirectional"))
      (node (ref "C9") (pin "1") (pinfunction "1_1") (pintype "bidirectional"))
      (node (ref "J1") (pin "1") (pinfunction "1_1") (pintype "passive"))
      (node (ref "J2") (pin "1") (pinfunction "1_1") (pintype "passive"))
      (node (ref "J3") (pin "1") (pinfunction "VCC_1") (pintype "bidirectional"))
      (node (ref "J5") (pin "1") (pinfunction "1_1") (pintype "passive"))
      (node (ref "J6") (pin "1") (pinfunction "1_1") (pintype "passive"))
      (node (ref "L1") (pin "2") (pinfunction "2_2") (pintype "bidirectional"))
      (node (ref "P9/P8") (pin "P9_3") (pinfunction "DC_3.3V0_P9_3") (pintype "bidirectional"))
      (node (ref "P9/P8") (pin "P9_4") (pinfunction "DC_3.3V1_P9_4") (pintype "bidirectional"))
      (node (ref "R2") (pin "2") (pinfunction "2_2") (pintype "passive"))
      (node (ref "R4") (pin "2") (pinfunction "2_2") (pintype "passive"))
      (node (ref "R5") (pin "1") (pinfunction "1_1") (pintype "passive"))
      (node (ref "R6") (pin "2") (pinfunction "2_2") (pintype "passive"))
      (node (ref "R7") (pin "2") (pinfunction "2_2") (pintype "passive"))
      (node (ref "U1") (pin "1") (pinfunction "VDDIO_1") (pintype "bidirectional"))
      (node (ref "U1") (pin "14") (pinfunction "VCC_14") (pintype "bidirectional"))
      (node (ref "U1") (pin "15") (pinfunction "VCCA_15") (pintype "bidirectional"))
      (node (ref "U10") (pin "5") (pinfunction "VOUT_5") (pintype "bidirectional"))
      (node (ref "U11") (pin "P$2") (pinfunction "S_P$2") (pintype "bidirectional"))
      (node (ref "U2") (pin "1") (pinfunction "VDDIO_1") (pintype "bidirectional"))
      (node (ref "U2") (pin "13") (pinfunction "VDD_13") (pintype "bidirectional"))
      (node (ref "U2") (pin "8") (pinfunction "VDDIO_8") (pintype "bidirectional"))
      (node (ref "U3") (pin "3") (pinfunction "VDD_3") (pintype "bidirectional"))
      (node (ref "U4") (pin "5") (pinfunction "VCC_5") (pintype "bidirectional"))
      (node (ref "U5") (pin "1") (pinfunction "VCC_1") (pintype "bidirectional"))
      (node (ref "U6") (pin "VCC") (pinfunction "VCC_VCC") (pintype "bidirectional"))
      (node (ref "U7") (pin "A2") (pinfunction "A2_A2") (pintype "bidirectional"))
      (node (ref "U7") (pin "VCC") (pinfunction "VCC_VCC") (pintype "bidirectional"))
      (node (ref "U9") (pin "VA") (pinfunction "VA_VA") (pintype "bidirectional"))
    )
    (net (code "53") (name "VDD") (class "Default")
      (node (ref "P9/P8") (pin "P9_5") (pinfunction "VDD_5V0_P9_5") (pintype "bidirectional"))
      (node (ref "P9/P8") (pin "P9_6") (pinfunction "VDD_5V1_P9_6") (pintype "bidirectional"))
    )
    (net (code "54") (name "unconnected-(J1-Pad5)") (class "Default")
      (node (ref "J1") (pin "5") (pinfunction "5_5") (pintype "passive"))
    )
    (net (code "55") (name "unconnected-(J2-Pad5)") (class "Default")
      (node (ref "J2") (pin "5") (pinfunction "5_5") (pintype "passive"))
    )
    (net (code "56") (name "unconnected-(J8-PAD1-PadNC1)") (class "Default")
      (node (ref "J8") (pin "NC1") (pinfunction "PAD1_NC1") (pintype "bidirectional"))
    )
    (net (code "57") (name "unconnected-(J8-PAD2-PadNC2)") (class "Default")
      (node (ref "J8") (pin "NC2") (pinfunction "PAD2_NC2") (pintype "bidirectional"))
    )
    (net (code "58") (name "unconnected-(P9/P8-AGND-PadP9_34)") (class "Default")
      (node (ref "P9/P8") (pin "P9_34") (pinfunction "AGND_P9_34") (pintype "bidirectional"))
    )
    (net (code "59") (name "unconnected-(P9/P8-AIN0-PadP9_39)") (class "Default")
      (node (ref "P9/P8") (pin "P9_39") (pinfunction "AIN0_P9_39") (pintype "bidirectional"))
    )
    (net (code "60") (name "unconnected-(P9/P8-AIN1-PadP9_40)") (class "Default")
      (node (ref "P9/P8") (pin "P9_40") (pinfunction "AIN1_P9_40") (pintype "bidirectional"))
    )
    (net (code "61") (name "unconnected-(P9/P8-AIN2-PadP9_37)") (class "Default")
      (node (ref "P9/P8") (pin "P9_37") (pinfunction "AIN2_P9_37") (pintype "bidirectional"))
    )
    (net (code "62") (name "unconnected-(P9/P8-AIN3-PadP9_38)") (class "Default")
      (node (ref "P9/P8") (pin "P9_38") (pinfunction "AIN3_P9_38") (pintype "bidirectional"))
    )
    (net (code "63") (name "unconnected-(P9/P8-AIN4-PadP9_33)") (class "Default")
      (node (ref "P9/P8") (pin "P9_33") (pinfunction "AIN4_P9_33") (pintype "bidirectional"))
    )
    (net (code "64") (name "unconnected-(P9/P8-AIN5-PadP9_36)") (class "Default")
      (node (ref "P9/P8") (pin "P9_36") (pinfunction "AIN5_P9_36") (pintype "bidirectional"))
    )
    (net (code "65") (name "unconnected-(P9/P8-AIN6-PadP9_35)") (class "Default")
      (node (ref "P9/P8") (pin "P9_35") (pinfunction "AIN6_P9_35") (pintype "bidirectional"))
    )
    (net (code "66") (name "unconnected-(P9/P8-CLKOUT2{slash}GPIO3_20-PadP9_41)") (class "Default")
      (node (ref "P9/P8") (pin "P9_41") (pinfunction "CLKOUT2/GPIO3_20_P9_41") (pintype "bidirectional"))
    )
    (net (code "67") (name "unconnected-(P9/P8-GPIO0_7{slash}GPIO3_18-PadP9_42)") (class "Default")
      (node (ref "P9/P8") (pin "P9_42") (pinfunction "GPIO0_7/GPIO3_18_P9_42") (pintype "bidirectional"))
    )
    (net (code "68") (name "unconnected-(P9/P8-GPIO3_21-PadP9_25)") (class "Default")
      (node (ref "P9/P8") (pin "P9_25") (pinfunction "GPIO3_21_P9_25") (pintype "bidirectional"))
    )
    (net (code "69") (name "unconnected-(P9/P8-PWR_BUT-PadP9_9)") (class "Default")
      (node (ref "P9/P8") (pin "P9_9") (pinfunction "PWR_BUT_P9_9") (pintype "bidirectional"))
    )
    (net (code "70") (name "unconnected-(P9/P8-SPI1_CS0-PadP9_28)") (class "Default")
      (node (ref "P9/P8") (pin "P9_28") (pinfunction "SPI1_CS0_P9_28") (pintype "bidirectional"))
    )
    (net (code "71") (name "unconnected-(P9/P8-SPI1_D0-PadP9_29)") (class "Default")
      (node (ref "P9/P8") (pin "P9_29") (pinfunction "SPI1_D0_P9_29") (pintype "bidirectional"))
    )
    (net (code "72") (name "unconnected-(P9/P8-SPI1_D1-PadP9_30)") (class "Default")
      (node (ref "P9/P8") (pin "P9_30") (pinfunction "SPI1_D1_P9_30") (pintype "bidirectional"))
    )
    (net (code "73") (name "unconnected-(P9/P8-SPI1_SCLK-PadP9_31)") (class "Default")
      (node (ref "P9/P8") (pin "P9_31") (pinfunction "SPI1_SCLK_P9_31") (pintype "bidirectional"))
    )
    (net (code "74") (name "unconnected-(P9/P8-SYS_RESETN-PadP9_10)") (class "Default")
      (node (ref "P9/P8") (pin "P9_10") (pinfunction "SYS_RESETN_P9_10") (pintype "bidirectional"))
    )
    (net (code "75") (name "unconnected-(P9/P8-VADC-PadP9_32)") (class "Default")
      (node (ref "P9/P8") (pin "P9_32") (pinfunction "VADC_P9_32") (pintype "bidirectional"))
    )
    (net (code "76") (name "unconnected-(U1-INT2-Pad9)") (class "Default")
      (node (ref "U1") (pin "9") (pinfunction "INT2_9") (pintype "bidirectional"))
    )
    (net (code "77") (name "unconnected-(U2-AUX_CL-Pad7)") (class "Default")
      (node (ref "U2") (pin "7") (pinfunction "AUX_CL_7") (pintype "bidirectional"))
    )
    (net (code "78") (name "unconnected-(U2-AUX_DA-Pad21)") (class "Default")
      (node (ref "U2") (pin "21") (pinfunction "AUX_DA_21") (pintype "bidirectional"))
    )
    (net (code "79") (name "unconnected-(U5-BATTERY-Pad31)") (class "Default")
      (node (ref "U5") (pin "31") (pinfunction "BATTERY_31") (pintype "bidirectional"))
    )
    (net (code "80") (name "unconnected-(U5-DGND_USB-Pad10)") (class "Default")
      (node (ref "U5") (pin "10") (pinfunction "DGND_USB_10") (pintype "bidirectional"))
    )
    (net (code "81") (name "unconnected-(U5-DVDD_USB-Pad13)") (class "Default")
      (node (ref "U5") (pin "13") (pinfunction "DVDD_USB_13") (pintype "bidirectional"))
    )
    (net (code "82") (name "unconnected-(U5-TCK-Pad4)") (class "Default")
      (node (ref "U5") (pin "4") (pinfunction "TCK_4") (pintype "bidirectional"))
    )
    (net (code "83") (name "unconnected-(U5-TDO-Pad5)") (class "Default")
      (node (ref "U5") (pin "5") (pinfunction "TDO_5") (pintype "bidirectional"))
    )
    (net (code "84") (name "unconnected-(U5-TMS-Pad3)") (class "Default")
      (node (ref "U5") (pin "3") (pinfunction "TMS_3") (pintype "bidirectional"))
    )
    (net (code "85") (name "unconnected-(U5-UNUSED-Pad2)") (class "Default")
      (node (ref "U5") (pin "2") (pinfunction "UNUSED_2") (pintype "bidirectional"))
    )
    (net (code "86") (name "unconnected-(U5-USB_N-Pad12)") (class "Default")
      (node (ref "U5") (pin "12") (pinfunction "USB_N_12") (pintype "bidirectional"))
    )
    (net (code "87") (name "unconnected-(U5-USB_P-Pad11)") (class "Default")
      (node (ref "U5") (pin "11") (pinfunction "USB_P_11") (pintype "bidirectional"))
    )
    (net (code "88") (name "unconnected-(U10-LOAD-Pad6)") (class "Default")
      (node (ref "U10") (pin "6") (pinfunction "LOAD_6") (pintype "bidirectional"))
    )
    (net (code "89") (name "unconnected-(U10-PG-Pad7)") (class "Default")
      (node (ref "U10") (pin "7") (pinfunction "PG_7") (pintype "bidirectional"))
    )
    (net (code "90") (name "~{ACCEL_CS}") (class "Default")
      (node (ref "J5") (pin "7") (pinfunction "7_7") (pintype "passive"))
      (node (ref "U2") (pin "22") (pinfunction "~{CS}_22") (pintype "bidirectional"))
      (node (ref "U5") (pin "9") (pinfunction "B3_9") (pintype "bidirectional"))
    )
    (net (code "91") (name "~{OBS_CS}") (class "Default")
      (node (ref "J1") (pin "8") (pinfunction "8_8") (pintype "passive"))
      (node (ref "J2") (pin "8") (pinfunction "8_8") (pintype "passive"))
      (node (ref "J6") (pin "8") (pinfunction "8_8") (pintype "passive"))
      (node (ref "J7") (pin "1") (pinfunction "1_1") (pintype "passive"))
      (node (ref "U5") (pin "28") (pinfunction "ADC6_28") (pintype "bidirectional"))
    )
    (net (code "92") (name "~{PRESSURE_CS}") (class "Default")
      (node (ref "J5") (pin "15") (pinfunction "15_15") (pintype "passive"))
      (node (ref "U1") (pin "8") (pinfunction "~{CS}_8") (pintype "bidirectional"))
      (node (ref "U5") (pin "20") (pinfunction "C1_20") (pintype "bidirectional"))
    )
    (net (code "93") (name "~{RESET0}") (class "Default")
      (node (ref "P9/P8") (pin "P9_12") (pinfunction "GPIO1_28_P9_12") (pintype "bidirectional"))
    )
    (net (code "94") (name "~{RESET2}") (class "Default")
      (node (ref "P9/P8") (pin "P9_11") (pinfunction "UART4_RXD_P9_11") (pintype "bidirectional"))
    )
    (net (code "95") (name "~{RESET}") (class "Default")
      (node (ref "J3") (pin "6") (pinfunction "~{RESET}_6") (pintype "bidirectional"))
      (node (ref "U5") (pin "30") (pinfunction "~{RESET}_30") (pintype "bidirectional"))
    )
  )
)
